# ESP32-S3_AT_UWB_Pro_with_Display_v1_0.net
KiCad netlist of a schematic drawn in EAGLE
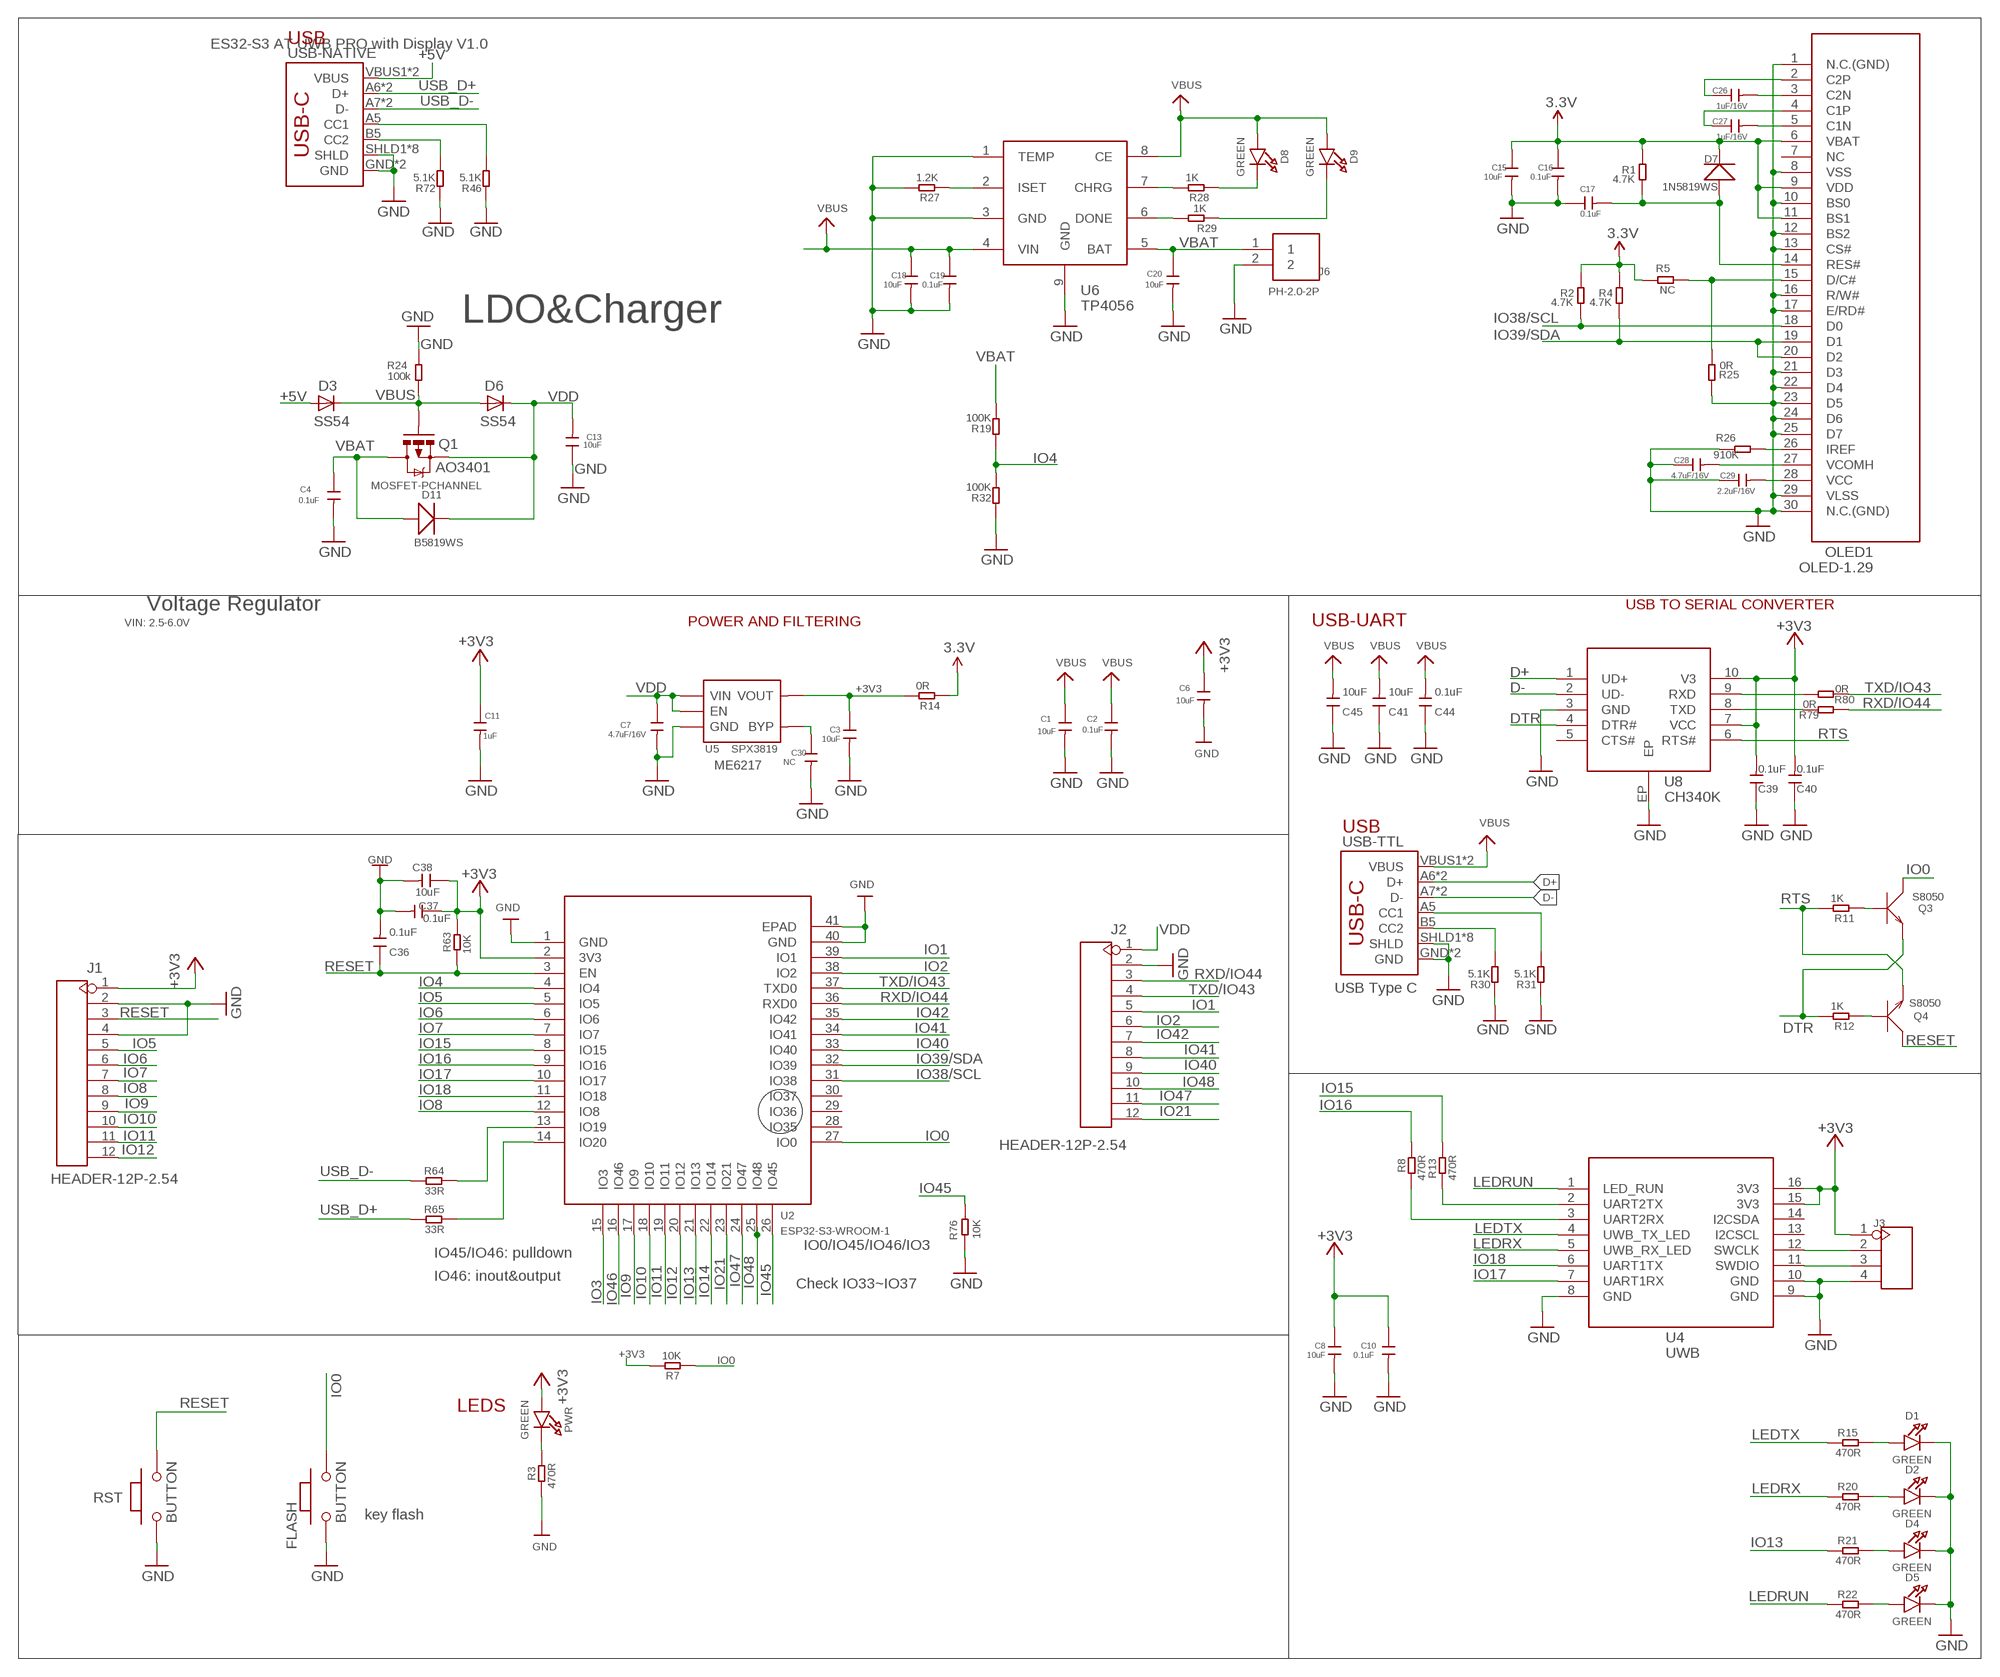
[diagram p0: schematic, sheet 1]

(export (version "E")
  (design (tool "Eeschema 10.0.6"))
  (components
    (comp (ref "C1")
      (value "10uF")
      (footprint "eagle-import:0603")
      (libsource (lib "eagle-import") (part "C-0603"))
    )
    (comp (ref "C2")
      (value "0.1uF")
      (footprint "eagle-import:0603")
      (libsource (lib "eagle-import") (part "C-0603"))
    )
    (comp (ref "C3")
      (value "10uF")
      (footprint "eagle-import:0603")
      (libsource (lib "eagle-import") (part "C-0603"))
    )
    (comp (ref "C4")
      (value "0.1uF")
      (footprint "eagle-import:0603")
      (libsource (lib "eagle-import") (part "C-0603"))
    )
    (comp (ref "C6")
      (value "10uF")
      (footprint "eagle-import:0603")
      (libsource (lib "eagle-import") (part "C-0603"))
    )
    (comp (ref "C7")
      (value "4.7uF/16V")
      (footprint "eagle-import:0603")
      (libsource (lib "eagle-import") (part "C-0603"))
    )
    (comp (ref "C8")
      (value "10uF")
      (footprint "eagle-import:0603")
      (libsource (lib "eagle-import") (part "C-0603"))
    )
    (comp (ref "C10")
      (value "0.1uF")
      (footprint "eagle-import:0603")
      (libsource (lib "eagle-import") (part "C-0603"))
    )
    (comp (ref "C11")
      (value "1uF")
      (footprint "eagle-import:0603")
      (libsource (lib "eagle-import") (part "C-0603"))
    )
    (comp (ref "C13")
      (value "10uF")
      (footprint "eagle-import:0603")
      (libsource (lib "eagle-import") (part "C-0603"))
    )
    (comp (ref "C15")
      (value "10uF")
      (footprint "eagle-import:0603")
      (libsource (lib "eagle-import") (part "C-0603"))
    )
    (comp (ref "C16")
      (value "0.1uF")
      (footprint "eagle-import:0603")
      (libsource (lib "eagle-import") (part "C-0603"))
    )
    (comp (ref "C17")
      (value "0.1uF")
      (footprint "eagle-import:0603")
      (libsource (lib "eagle-import") (part "C-0603"))
    )
    (comp (ref "C18")
      (value "10uF")
      (footprint "eagle-import:0603")
      (libsource (lib "eagle-import") (part "C-0603"))
    )
    (comp (ref "C19")
      (value "0.1uF")
      (footprint "eagle-import:0603")
      (libsource (lib "eagle-import") (part "C-0603"))
    )
    (comp (ref "C20")
      (value "10uF")
      (footprint "eagle-import:0603")
      (libsource (lib "eagle-import") (part "C-0603"))
    )
    (comp (ref "C26")
      (value "1uF/16V")
      (footprint "eagle-import:0603")
      (libsource (lib "eagle-import") (part "C-0603"))
    )
    (comp (ref "C27")
      (value "1uF/16V")
      (footprint "eagle-import:0603")
      (libsource (lib "eagle-import") (part "C-0603"))
    )
    (comp (ref "C28")
      (value "4.7uF/16V")
      (footprint "eagle-import:0603")
      (libsource (lib "eagle-import") (part "C-0603"))
    )
    (comp (ref "C29")
      (value "2.2uF/16V")
      (footprint "eagle-import:0603")
      (libsource (lib "eagle-import") (part "C-0603"))
    )
    (comp (ref "C30")
      (value "NC")
      (footprint "eagle-import:0603")
      (libsource (lib "eagle-import") (part "C-0603"))
    )
    (comp (ref "C36")
      (value "0.1uF")
      (footprint "eagle-import:DISCRETE_C0603")
      (libsource (lib "eagle-import") (part "DISCRETE_C-0603"))
    )
    (comp (ref "C37")
      (value "0.1uF")
      (footprint "eagle-import:DISCRETE_C0603")
      (libsource (lib "eagle-import") (part "DISCRETE_C-0603"))
    )
    (comp (ref "C38")
      (value "10uF")
      (footprint "eagle-import:DISCRETE_C0603")
      (libsource (lib "eagle-import") (part "DISCRETE_C-0603"))
    )
    (comp (ref "C39")
      (value "0.1uF")
      (footprint "eagle-import:DISCRETE_C0603")
      (libsource (lib "eagle-import") (part "DISCRETE_C-0603"))
    )
    (comp (ref "C40")
      (value "0.1uF")
      (footprint "eagle-import:DISCRETE_C0603")
      (libsource (lib "eagle-import") (part "DISCRETE_C-0603"))
    )
    (comp (ref "C41")
      (value "10uF")
      (footprint "eagle-import:DISCRETE_C0603")
      (libsource (lib "eagle-import") (part "DISCRETE_C-0603"))
    )
    (comp (ref "C44")
      (value "0.1uF")
      (footprint "eagle-import:DISCRETE_C0603")
      (libsource (lib "eagle-import") (part "DISCRETE_C-0603"))
    )
    (comp (ref "C45")
      (value "10uF")
      (footprint "eagle-import:DISCRETE_C0603")
      (libsource (lib "eagle-import") (part "DISCRETE_C-0603"))
    )
    (comp (ref "D1")
      (value "GREEN")
      (footprint "eagle-import:CHIPLED_0805_NOOUTLINE")
      (libsource (lib "eagle-import") (part "LED0805_NOOUTLINE"))
    )
    (comp (ref "D2")
      (value "GREEN")
      (footprint "eagle-import:CHIPLED_0805_NOOUTLINE")
      (libsource (lib "eagle-import") (part "LED0805_NOOUTLINE"))
    )
    (comp (ref "D3")
      (value "SS54")
      (footprint "eagle-import:DO-214AC")
      (libsource (lib "eagle-import") (part "DIODE-DO-214AC"))
    )
    (comp (ref "D4")
      (value "GREEN")
      (footprint "eagle-import:CHIPLED_0805_NOOUTLINE")
      (libsource (lib "eagle-import") (part "LED0805_NOOUTLINE"))
    )
    (comp (ref "D5")
      (value "GREEN")
      (footprint "eagle-import:CHIPLED_0805_NOOUTLINE")
      (libsource (lib "eagle-import") (part "LED0805_NOOUTLINE"))
    )
    (comp (ref "D6")
      (value "SS54")
      (footprint "eagle-import:DO-214AC")
      (libsource (lib "eagle-import") (part "DIODE-DO-214AC"))
    )
    (comp (ref "D7")
      (value "1N5819WS")
      (footprint "eagle-import:SOD323")
      (libsource (lib "eagle-import") (part "D'0805'"))
    )
    (comp (ref "D8")
      (value "GREEN")
      (footprint "eagle-import:CHIPLED_0805_NOOUTLINE")
      (libsource (lib "eagle-import") (part "LED0805_NOOUTLINE"))
    )
    (comp (ref "D9")
      (value "GREEN")
      (footprint "eagle-import:CHIPLED_0805_NOOUTLINE")
      (libsource (lib "eagle-import") (part "LED0805_NOOUTLINE"))
    )
    (comp (ref "D11")
      (value "B5819WS")
      (footprint "eagle-import:SOD323")
      (libsource (lib "eagle-import") (part "D'0805'"))
    )
    (comp (ref "FLASH")
      (value "BUTTON")
      (footprint "eagle-import:157SW")
      (libsource (lib "eagle-import") (part "PB157"))
    )
    (comp (ref "J1")
      (value "HEADER-12P-2.54")
      (footprint "eagle-import:12P-2.54")
      (libsource (lib "eagle-import") (part "HEADER-12P-2.54"))
    )
    (comp (ref "J2")
      (value "HEADER-12P-2.54")
      (footprint "eagle-import:12P-2.54")
      (libsource (lib "eagle-import") (part "HEADER-12P-2.54"))
    )
    (comp (ref "J3")
      (value "HEADER-4P-60/35MILROUND")
      (footprint "eagle-import:4P-65_35ROUND")
      (libsource (lib "eagle-import") (part "HEADER-4P-60/35MILROUND"))
    )
    (comp (ref "J6")
      (value "PH-2.0-2P")
      (footprint "eagle-import:PH-2.0-2P")
      (libsource (lib "eagle-import") (part "PH-2.0-2P"))
    )
    (comp (ref "OLED1")
      (value "OLED-1.29")
      (footprint "eagle-import:OLED-1.29")
      (libsource (lib "eagle-import") (part "OLED-1.29"))
    )
    (comp (ref "PWR")
      (value "GREEN")
      (footprint "eagle-import:CHIPLED_0805_NOOUTLINE")
      (libsource (lib "eagle-import") (part "LED0805_NOOUTLINE"))
    )
    (comp (ref "Q1")
      (value "MOSFET-PCHANNEL")
      (footprint "eagle-import:SOT23-3")
      (libsource (lib "eagle-import") (part "MOSFET-PCHANNEL"))
    )
    (comp (ref "Q3")
      (value "S8050")
      (footprint "eagle-import:SOT23")
      (libsource (lib "eagle-import") (part "TRANSISTOR-NPN-SOT23"))
    )
    (comp (ref "Q4")
      (value "S8050")
      (footprint "eagle-import:SOT23")
      (libsource (lib "eagle-import") (part "TRANSISTOR-NPN-SOT23"))
    )
    (comp (ref "R1")
      (value "4.7K")
      (footprint "eagle-import:R0603")
      (libsource (lib "eagle-import") (part "R-0603"))
    )
    (comp (ref "R2")
      (value "4.7K")
      (footprint "eagle-import:R0603")
      (libsource (lib "eagle-import") (part "R-0603"))
    )
    (comp (ref "R3")
      (value "470R")
      (footprint "eagle-import:R0603")
      (libsource (lib "eagle-import") (part "R-0603"))
    )
    (comp (ref "R4")
      (value "4.7K")
      (footprint "eagle-import:R0603")
      (libsource (lib "eagle-import") (part "R-0603"))
    )
    (comp (ref "R5")
      (value "NC")
      (footprint "eagle-import:R0603")
      (libsource (lib "eagle-import") (part "R-0603"))
    )
    (comp (ref "R7")
      (value "10K")
      (footprint "eagle-import:R0603")
      (libsource (lib "eagle-import") (part "R-0603"))
    )
    (comp (ref "R8")
      (value "470R")
      (footprint "eagle-import:R0603")
      (libsource (lib "eagle-import") (part "R-0603"))
    )
    (comp (ref "R11")
      (value "1K")
      (footprint "eagle-import:R0603")
      (libsource (lib "eagle-import") (part "R-0603"))
    )
    (comp (ref "R12")
      (value "1K")
      (footprint "eagle-import:R0603")
      (libsource (lib "eagle-import") (part "R-0603"))
    )
    (comp (ref "R13")
      (value "470R")
      (footprint "eagle-import:R0603")
      (libsource (lib "eagle-import") (part "R-0603"))
    )
    (comp (ref "R14")
      (value "0R")
      (footprint "eagle-import:R0603")
      (libsource (lib "eagle-import") (part "R-0603"))
    )
    (comp (ref "R15")
      (value "470R")
      (footprint "eagle-import:R0603")
      (libsource (lib "eagle-import") (part "R-0603"))
    )
    (comp (ref "R19")
      (value "100K")
      (footprint "eagle-import:DISCRETE_R0603")
      (libsource (lib "eagle-import") (part "DISCRETE_R-0603"))
    )
    (comp (ref "R20")
      (value "470R")
      (footprint "eagle-import:R0603")
      (libsource (lib "eagle-import") (part "R-0603"))
    )
    (comp (ref "R21")
      (value "470R")
      (footprint "eagle-import:R0603")
      (libsource (lib "eagle-import") (part "R-0603"))
    )
    (comp (ref "R22")
      (value "470R")
      (footprint "eagle-import:R0603")
      (libsource (lib "eagle-import") (part "R-0603"))
    )
    (comp (ref "R24")
      (value "100k")
      (footprint "eagle-import:R0603")
      (libsource (lib "eagle-import") (part "R-0603"))
    )
    (comp (ref "R25")
      (value "0R")
      (footprint "eagle-import:R0603")
      (libsource (lib "eagle-import") (part "R-0603"))
    )
    (comp (ref "R26")
      (value "910K")
      (footprint "eagle-import:R0603")
      (libsource (lib "eagle-import") (part "R-0603"))
    )
    (comp (ref "R27")
      (value "1.2K")
      (footprint "eagle-import:R0603")
      (libsource (lib "eagle-import") (part "R-0603"))
    )
    (comp (ref "R28")
      (value "1K")
      (footprint "eagle-import:R0603")
      (libsource (lib "eagle-import") (part "R-0603"))
    )
    (comp (ref "R29")
      (value "1K")
      (footprint "eagle-import:R0603")
      (libsource (lib "eagle-import") (part "R-0603"))
    )
    (comp (ref "R30")
      (value "5.1K")
      (footprint "eagle-import:DISCRETE_R0603")
      (libsource (lib "eagle-import") (part "DISCRETE_R-0603"))
    )
    (comp (ref "R31")
      (value "5.1K")
      (footprint "eagle-import:DISCRETE_R0603")
      (libsource (lib "eagle-import") (part "DISCRETE_R-0603"))
    )
    (comp (ref "R32")
      (value "100K")
      (footprint "eagle-import:DISCRETE_R0603")
      (libsource (lib "eagle-import") (part "DISCRETE_R-0603"))
    )
    (comp (ref "R46")
      (value "5.1K")
      (footprint "eagle-import:DISCRETE_R0603")
      (libsource (lib "eagle-import") (part "DISCRETE_R-0603"))
    )
    (comp (ref "R63")
      (value "10K")
      (footprint "eagle-import:R0603")
      (libsource (lib "eagle-import") (part "R-0603"))
    )
    (comp (ref "R64")
      (value "33R")
      (footprint "eagle-import:R0603")
      (libsource (lib "eagle-import") (part "R-0603"))
    )
    (comp (ref "R65")
      (value "33R")
      (footprint "eagle-import:R0603")
      (libsource (lib "eagle-import") (part "R-0603"))
    )
    (comp (ref "R72")
      (value "5.1K")
      (footprint "eagle-import:DISCRETE_R0603")
      (libsource (lib "eagle-import") (part "DISCRETE_R-0603"))
    )
    (comp (ref "R76")
      (value "10K")
      (footprint "eagle-import:R0603")
      (libsource (lib "eagle-import") (part "R-0603"))
    )
    (comp (ref "R79")
      (value "0R")
      (footprint "eagle-import:R0603")
      (libsource (lib "eagle-import") (part "R-0603"))
    )
    (comp (ref "R80")
      (value "0R")
      (footprint "eagle-import:R0603")
      (libsource (lib "eagle-import") (part "R-0603"))
    )
    (comp (ref "RST")
      (value "BUTTON")
      (footprint "eagle-import:157SW")
      (libsource (lib "eagle-import") (part "PB157"))
    )
    (comp (ref "U2")
      (value "ESP32-S3-WROOM-1")
      (footprint "eagle-import:ESP32-S3-WROOM-1")
      (libsource (lib "eagle-import") (part "ESP32-S3-WROOM-1"))
    )
    (comp (ref "U4")
      (value "UWB")
      (footprint "eagle-import:UWB")
      (libsource (lib "eagle-import") (part "UWB"))
    )
    (comp (ref "U5")
      (value "SPX3819")
      (footprint "eagle-import:SOT23-5")
      (libsource (lib "eagle-import") (part "SPX3819"))
    )
    (comp (ref "U6")
      (value "TP4056")
      (footprint "eagle-import:SOP8-1.27P")
      (libsource (lib "eagle-import") (part "TP4056"))
    )
    (comp (ref "U8")
      (value "CH340K")
      (footprint "eagle-import:ESOP-10-EP-150MIL")
      (libsource (lib "eagle-import") (part "CH340K"))
    )
    (comp (ref "USB-NATIVE")
      (value "USB_C5")
      (footprint "eagle-import:USB-C-16P-5")
      (libsource (lib "eagle-import") (part "USB_C5"))
    )
    (comp (ref "USB-TTL")
      (value "USB_C5")
      (footprint "eagle-import:USB-C-16P-5")
      (libsource (lib "eagle-import") (part "USB_C5"))
    )
  )
  (nets
    (net (code "1") (name "+3V3") (class "Default")
      (node (ref "C10") (pin "1") (pinfunction "1_1") (pintype "passive"))
      (node (ref "C11") (pin "1") (pinfunction "1_1") (pintype "passive"))
      (node (ref "C3") (pin "1") (pinfunction "1_1") (pintype "passive"))
      (node (ref "C37") (pin "1") (pinfunction "1_1") (pintype "passive"))
      (node (ref "C38") (pin "1") (pinfunction "1_1") (pintype "passive"))
      (node (ref "C39") (pin "2") (pinfunction "2_2") (pintype "passive"))
      (node (ref "C40") (pin "2") (pinfunction "2_2") (pintype "passive"))
      (node (ref "C6") (pin "1") (pinfunction "1_1") (pintype "passive"))
      (node (ref "C8") (pin "1") (pinfunction "1_1") (pintype "passive"))
      (node (ref "J1") (pin "1") (pinfunction "1_1") (pintype "bidirectional"))
      (node (ref "J3") (pin "1") (pinfunction "P$1_1") (pintype "bidirectional"))
      (node (ref "PWR") (pin "A") (pinfunction "A_A") (pintype "passive"))
      (node (ref "R14") (pin "2") (pinfunction "2_2") (pintype "passive"))
      (node (ref "R63") (pin "2") (pinfunction "2_2") (pintype "passive"))
      (node (ref "R7") (pin "2") (pinfunction "2_2") (pintype "passive"))
      (node (ref "U2") (pin "2") (pinfunction "3V3_2") (pintype "bidirectional"))
      (node (ref "U4") (pin "15") (pinfunction "3V3_15") (pintype "bidirectional"))
      (node (ref "U4") (pin "16") (pinfunction "3V3_16") (pintype "bidirectional"))
      (node (ref "U5") (pin "5") (pinfunction "VOUT_5") (pintype "bidirectional"))
      (node (ref "U8") (pin "10") (pinfunction "V3_10") (pintype "bidirectional"))
      (node (ref "U8") (pin "7") (pinfunction "VCC_7") (pintype "bidirectional"))
    )
    (net (code "2") (name "/+5V") (class "Default")
      (node (ref "D3") (pin "A") (pinfunction "A_A") (pintype "passive"))
      (node (ref "USB-NATIVE") (pin "VBUS1") (pinfunction "VBUS_VBUS1") (pintype "bidirectional"))
      (node (ref "USB-NATIVE") (pin "VBUS2") (pinfunction "VBUS_VBUS2") (pintype "bidirectional"))
    )
    (net (code "3") (name "/DTR") (class "Default")
      (node (ref "Q3") (pin "2") (pinfunction "E_2") (pintype "passive"))
      (node (ref "R12") (pin "2") (pinfunction "2_2") (pintype "passive"))
      (node (ref "U8") (pin "4") (pinfunction "DTR#_4") (pintype "bidirectional"))
    )
    (net (code "4") (name "/IO0") (class "Default")
      (node (ref "FLASH") (pin "2") (pinfunction "2_2") (pintype "passive"))
      (node (ref "Q3") (pin "3") (pinfunction "C_3") (pintype "passive"))
      (node (ref "R7") (pin "1") (pinfunction "1_1") (pintype "passive"))
      (node (ref "U2") (pin "27") (pinfunction "IO0_27") (pintype "bidirectional"))
    )
    (net (code "5") (name "/IO1") (class "Default")
      (node (ref "J2") (pin "5") (pinfunction "5_5") (pintype "bidirectional"))
      (node (ref "U2") (pin "39") (pinfunction "IO1_39") (pintype "bidirectional"))
    )
    (net (code "6") (name "/IO2") (class "Default")
      (node (ref "J2") (pin "6") (pinfunction "6_6") (pintype "bidirectional"))
      (node (ref "U2") (pin "38") (pinfunction "IO2_38") (pintype "bidirectional"))
    )
    (net (code "7") (name "/IO3") (class "Default")
      (node (ref "U2") (pin "15") (pinfunction "IO3_15") (pintype "bidirectional"))
    )
    (net (code "8") (name "/IO4") (class "Default")
      (node (ref "R19") (pin "1") (pinfunction "1_1") (pintype "passive"))
      (node (ref "R32") (pin "2") (pinfunction "2_2") (pintype "passive"))
      (node (ref "U2") (pin "4") (pinfunction "IO4_4") (pintype "bidirectional"))
    )
    (net (code "9") (name "/IO5") (class "Default")
      (node (ref "J1") (pin "5") (pinfunction "5_5") (pintype "bidirectional"))
      (node (ref "U2") (pin "5") (pinfunction "IO5_5") (pintype "bidirectional"))
    )
    (net (code "10") (name "/IO6") (class "Default")
      (node (ref "J1") (pin "6") (pinfunction "6_6") (pintype "bidirectional"))
      (node (ref "U2") (pin "6") (pinfunction "IO6_6") (pintype "bidirectional"))
    )
    (net (code "11") (name "/IO7") (class "Default")
      (node (ref "J1") (pin "7") (pinfunction "7_7") (pintype "bidirectional"))
      (node (ref "U2") (pin "7") (pinfunction "IO7_7") (pintype "bidirectional"))
    )
    (net (code "12") (name "/IO8") (class "Default")
      (node (ref "J1") (pin "8") (pinfunction "8_8") (pintype "bidirectional"))
      (node (ref "U2") (pin "12") (pinfunction "IO8_12") (pintype "bidirectional"))
    )
    (net (code "13") (name "/IO9") (class "Default")
      (node (ref "J1") (pin "9") (pinfunction "9_9") (pintype "bidirectional"))
      (node (ref "U2") (pin "17") (pinfunction "IO9_17") (pintype "bidirectional"))
    )
    (net (code "14") (name "/IO10") (class "Default")
      (node (ref "J1") (pin "10") (pinfunction "10_10") (pintype "bidirectional"))
      (node (ref "U2") (pin "18") (pinfunction "IO10_18") (pintype "bidirectional"))
    )
    (net (code "15") (name "/IO11") (class "Default")
      (node (ref "J1") (pin "11") (pinfunction "11_11") (pintype "bidirectional"))
      (node (ref "U2") (pin "19") (pinfunction "IO11_19") (pintype "bidirectional"))
    )
    (net (code "16") (name "/IO12") (class "Default")
      (node (ref "J1") (pin "12") (pinfunction "12_12") (pintype "bidirectional"))
      (node (ref "U2") (pin "20") (pinfunction "IO12_20") (pintype "bidirectional"))
    )
    (net (code "17") (name "/IO13") (class "Default")
      (node (ref "R21") (pin "1") (pinfunction "1_1") (pintype "passive"))
      (node (ref "U2") (pin "21") (pinfunction "IO13_21") (pintype "bidirectional"))
    )
    (net (code "18") (name "/IO14") (class "Default")
      (node (ref "U2") (pin "22") (pinfunction "IO14_22") (pintype "bidirectional"))
    )
    (net (code "19") (name "/IO15") (class "Default")
      (node (ref "R13") (pin "2") (pinfunction "2_2") (pintype "passive"))
      (node (ref "U2") (pin "8") (pinfunction "IO15_8") (pintype "bidirectional"))
    )
    (net (code "20") (name "/IO16") (class "Default")
      (node (ref "R8") (pin "2") (pinfunction "2_2") (pintype "passive"))
      (node (ref "U2") (pin "9") (pinfunction "IO16_9") (pintype "bidirectional"))
    )
    (net (code "21") (name "/IO17") (class "Default")
      (node (ref "U2") (pin "10") (pinfunction "IO17_10") (pintype "bidirectional"))
      (node (ref "U4") (pin "7") (pinfunction "UART1RX_7") (pintype "bidirectional"))
    )
    (net (code "22") (name "/IO18") (class "Default")
      (node (ref "U2") (pin "11") (pinfunction "IO18_11") (pintype "bidirectional"))
      (node (ref "U4") (pin "6") (pinfunction "UART1TX_6") (pintype "bidirectional"))
    )
    (net (code "23") (name "/IO21") (class "Default")
      (node (ref "J2") (pin "12") (pinfunction "12_12") (pintype "bidirectional"))
      (node (ref "U2") (pin "23") (pinfunction "IO21_23") (pintype "bidirectional"))
    )
    (net (code "24") (name "/IO38{slash}SCL") (class "Default")
      (node (ref "OLED1") (pin "18") (pinfunction "D0_18") (pintype "bidirectional"))
      (node (ref "R2") (pin "1") (pinfunction "1_1") (pintype "passive"))
      (node (ref "U2") (pin "31") (pinfunction "IO38_31") (pintype "bidirectional"))
    )
    (net (code "25") (name "/IO39{slash}SDA") (class "Default")
      (node (ref "OLED1") (pin "19") (pinfunction "D1_19") (pintype "bidirectional"))
      (node (ref "OLED1") (pin "20") (pinfunction "D2_20") (pintype "bidirectional"))
      (node (ref "R4") (pin "1") (pinfunction "1_1") (pintype "passive"))
      (node (ref "U2") (pin "32") (pinfunction "IO39_32") (pintype "bidirectional"))
    )
    (net (code "26") (name "/IO40") (class "Default")
      (node (ref "J2") (pin "9") (pinfunction "9_9") (pintype "bidirectional"))
      (node (ref "U2") (pin "33") (pinfunction "IO40_33") (pintype "bidirectional"))
    )
    (net (code "27") (name "/IO41") (class "Default")
      (node (ref "J2") (pin "8") (pinfunction "8_8") (pintype "bidirectional"))
      (node (ref "U2") (pin "34") (pinfunction "IO41_34") (pintype "bidirectional"))
    )
    (net (code "28") (name "/IO42") (class "Default")
      (node (ref "J2") (pin "7") (pinfunction "7_7") (pintype "bidirectional"))
      (node (ref "U2") (pin "35") (pinfunction "IO42_35") (pintype "bidirectional"))
    )
    (net (code "29") (name "/IO45") (class "Default")
      (node (ref "R76") (pin "2") (pinfunction "2_2") (pintype "passive"))
      (node (ref "U2") (pin "26") (pinfunction "IO45_26") (pintype "bidirectional"))
    )
    (net (code "30") (name "/IO46") (class "Default")
      (node (ref "U2") (pin "16") (pinfunction "IO46_16") (pintype "bidirectional"))
    )
    (net (code "31") (name "/IO47") (class "Default")
      (node (ref "J2") (pin "11") (pinfunction "11_11") (pintype "bidirectional"))
      (node (ref "U2") (pin "24") (pinfunction "IO47_24") (pintype "bidirectional"))
    )
    (net (code "32") (name "/IO48") (class "Default")
      (node (ref "J2") (pin "10") (pinfunction "10_10") (pintype "bidirectional"))
      (node (ref "U2") (pin "25") (pinfunction "IO48_25") (pintype "bidirectional"))
    )
    (net (code "33") (name "/LEDRUN") (class "Default")
      (node (ref "R22") (pin "1") (pinfunction "1_1") (pintype "passive"))
      (node (ref "U4") (pin "1") (pinfunction "LED_RUN_1") (pintype "bidirectional"))
    )
    (net (code "34") (name "/LEDRX") (class "Default")
      (node (ref "R20") (pin "1") (pinfunction "1_1") (pintype "passive"))
      (node (ref "U4") (pin "5") (pinfunction "UWB_RX_LED_5") (pintype "bidirectional"))
    )
    (net (code "35") (name "/LEDTX") (class "Default")
      (node (ref "R15") (pin "1") (pinfunction "1_1") (pintype "passive"))
      (node (ref "U4") (pin "4") (pinfunction "UWB_TX_LED_4") (pintype "bidirectional"))
    )
    (net (code "36") (name "/RESET") (class "Default")
      (node (ref "C36") (pin "1") (pinfunction "1_1") (pintype "passive"))
      (node (ref "J1") (pin "3") (pinfunction "3_3") (pintype "bidirectional"))
      (node (ref "Q4") (pin "3") (pinfunction "C_3") (pintype "passive"))
      (node (ref "R63") (pin "1") (pinfunction "1_1") (pintype "passive"))
      (node (ref "RST") (pin "2") (pinfunction "2_2") (pintype "passive"))
      (node (ref "U2") (pin "3") (pinfunction "EN_3") (pintype "bidirectional"))
    )
    (net (code "37") (name "/RTS") (class "Default")
      (node (ref "Q4") (pin "2") (pinfunction "E_2") (pintype "passive"))
      (node (ref "R11") (pin "2") (pinfunction "2_2") (pintype "passive"))
      (node (ref "U8") (pin "6") (pinfunction "RTS#_6") (pintype "bidirectional"))
    )
    (net (code "38") (name "/RXD{slash}IO44") (class "Default")
      (node (ref "J2") (pin "3") (pinfunction "3_3") (pintype "bidirectional"))
      (node (ref "R79") (pin "1") (pinfunction "1_1") (pintype "passive"))
      (node (ref "U2") (pin "36") (pinfunction "RXD0_36") (pintype "bidirectional"))
    )
    (net (code "39") (name "/TXD{slash}IO43") (class "Default")
      (node (ref "J2") (pin "4") (pinfunction "4_4") (pintype "bidirectional"))
      (node (ref "R80") (pin "1") (pinfunction "1_1") (pintype "passive"))
      (node (ref "U2") (pin "37") (pinfunction "TXD0_37") (pintype "bidirectional"))
    )
    (net (code "40") (name "/USB_D+") (class "Default")
      (node (ref "R65") (pin "1") (pinfunction "1_1") (pintype "passive"))
      (node (ref "USB-NATIVE") (pin "A6") (pinfunction "D+_A6") (pintype "bidirectional"))
      (node (ref "USB-NATIVE") (pin "B6") (pinfunction "D+_B6") (pintype "bidirectional"))
    )
    (net (code "41") (name "/USB_D-") (class "Default")
      (node (ref "R64") (pin "1") (pinfunction "1_1") (pintype "passive"))
      (node (ref "USB-NATIVE") (pin "A7") (pinfunction "D-_A7") (pintype "bidirectional"))
      (node (ref "USB-NATIVE") (pin "B7") (pinfunction "D-_B7") (pintype "bidirectional"))
    )
    (net (code "42") (name "/VBAT") (class "Default")
      (node (ref "C20") (pin "1") (pinfunction "1_1") (pintype "passive"))
      (node (ref "C4") (pin "1") (pinfunction "1_1") (pintype "passive"))
      (node (ref "D11") (pin "+") (pinfunction "+_+") (pintype "passive"))
      (node (ref "J6") (pin "1") (pinfunction "1_1") (pintype "bidirectional"))
      (node (ref "Q1") (pin "3") (pinfunction "D_3") (pintype "passive"))
      (node (ref "R19") (pin "2") (pinfunction "2_2") (pintype "passive"))
      (node (ref "U6") (pin "5") (pinfunction "BAT_5") (pintype "bidirectional"))
    )
    (net (code "43") (name "/VDD") (class "Default")
      (node (ref "C13") (pin "2") (pinfunction "2_2") (pintype "passive"))
      (node (ref "C7") (pin "1") (pinfunction "1_1") (pintype "passive"))
      (node (ref "D11") (pin "-") (pinfunction "-_-") (pintype "passive"))
      (node (ref "D6") (pin "C") (pinfunction "C_C") (pintype "passive"))
      (node (ref "J2") (pin "1") (pinfunction "1_1") (pintype "bidirectional"))
      (node (ref "Q1") (pin "2") (pinfunction "S_2") (pintype "passive"))
      (node (ref "U5") (pin "1") (pinfunction "VIN_1") (pintype "bidirectional"))
      (node (ref "U5") (pin "3") (pinfunction "EN_3") (pintype "bidirectional"))
    )
    (net (code "44") (name "3.3V") (class "Default")
      (node (ref "C15") (pin "1") (pinfunction "1_1") (pintype "passive"))
      (node (ref "C16") (pin "1") (pinfunction "1_1") (pintype "passive"))
      (node (ref "D7") (pin "-") (pinfunction "-_-") (pintype "passive"))
      (node (ref "OLED1") (pin "11") (pinfunction "BS1_11") (pintype "bidirectional"))
      (node (ref "OLED1") (pin "6") (pinfunction "VBAT_6") (pintype "bidirectional"))
      (node (ref "OLED1") (pin "9") (pinfunction "VDD_9") (pintype "bidirectional"))
      (node (ref "R1") (pin "2") (pinfunction "2_2") (pintype "passive"))
      (node (ref "R14") (pin "1") (pinfunction "1_1") (pintype "passive"))
      (node (ref "R2") (pin "2") (pinfunction "2_2") (pintype "passive"))
      (node (ref "R4") (pin "2") (pinfunction "2_2") (pintype "passive"))
      (node (ref "R5") (pin "2") (pinfunction "2_2") (pintype "passive"))
    )
    (net (code "45") (name "D+") (class "Default")
      (node (ref "U8") (pin "1") (pinfunction "UD+_1") (pintype "bidirectional"))
      (node (ref "USB-TTL") (pin "A6") (pinfunction "D+_A6") (pintype "bidirectional"))
      (node (ref "USB-TTL") (pin "B6") (pinfunction "D+_B6") (pintype "bidirectional"))
    )
    (net (code "46") (name "D-") (class "Default")
      (node (ref "U8") (pin "2") (pinfunction "UD-_2") (pintype "bidirectional"))
      (node (ref "USB-TTL") (pin "A7") (pinfunction "D-_A7") (pintype "bidirectional"))
      (node (ref "USB-TTL") (pin "B7") (pinfunction "D-_B7") (pintype "bidirectional"))
    )
    (net (code "47") (name "GND") (class "Default")
      (node (ref "C1") (pin "2") (pinfunction "2_2") (pintype "passive"))
      (node (ref "C10") (pin "2") (pinfunction "2_2") (pintype "passive"))
      (node (ref "C11") (pin "2") (pinfunction "2_2") (pintype "passive"))
      (node (ref "C13") (pin "1") (pinfunction "1_1") (pintype "passive"))
      (node (ref "C15") (pin "2") (pinfunction "2_2") (pintype "passive"))
      (node (ref "C16") (pin "2") (pinfunction "2_2") (pintype "passive"))
      (node (ref "C17") (pin "1") (pinfunction "1_1") (pintype "passive"))
      (node (ref "C18") (pin "2") (pinfunction "2_2") (pintype "passive"))
      (node (ref "C19") (pin "2") (pinfunction "2_2") (pintype "passive"))
      (node (ref "C2") (pin "2") (pinfunction "2_2") (pintype "passive"))
      (node (ref "C20") (pin "2") (pinfunction "2_2") (pintype "passive"))
      (node (ref "C28") (pin "1") (pinfunction "1_1") (pintype "passive"))
      (node (ref "C29") (pin "1") (pinfunction "1_1") (pintype "passive"))
      (node (ref "C3") (pin "2") (pinfunction "2_2") (pintype "passive"))
      (node (ref "C30") (pin "2") (pinfunction "2_2") (pintype "passive"))
      (node (ref "C36") (pin "2") (pinfunction "2_2") (pintype "passive"))
      (node (ref "C37") (pin "2") (pinfunction "2_2") (pintype "passive"))
      (node (ref "C38") (pin "2") (pinfunction "2_2") (pintype "passive"))
      (node (ref "C39") (pin "1") (pinfunction "1_1") (pintype "passive"))
      (node (ref "C4") (pin "2") (pinfunction "2_2") (pintype "passive"))
      (node (ref "C40") (pin "1") (pinfunction "1_1") (pintype "passive"))
      (node (ref "C41") (pin "1") (pinfunction "1_1") (pintype "passive"))
      (node (ref "C44") (pin "1") (pinfunction "1_1") (pintype "passive"))
      (node (ref "C45") (pin "1") (pinfunction "1_1") (pintype "passive"))
      (node (ref "C6") (pin "2") (pinfunction "2_2") (pintype "passive"))
      (node (ref "C7") (pin "2") (pinfunction "2_2") (pintype "passive"))
      (node (ref "C8") (pin "2") (pinfunction "2_2") (pintype "passive"))
      (node (ref "D1") (pin "C") (pinfunction "C_C") (pintype "passive"))
      (node (ref "D2") (pin "C") (pinfunction "C_C") (pintype "passive"))
      (node (ref "D4") (pin "C") (pinfunction "C_C") (pintype "passive"))
      (node (ref "D5") (pin "C") (pinfunction "C_C") (pintype "passive"))
      (node (ref "FLASH") (pin "1") (pinfunction "1_1") (pintype "passive"))
      (node (ref "J1") (pin "2") (pinfunction "2_2") (pintype "bidirectional"))
      (node (ref "J1") (pin "4") (pinfunction "4_4") (pintype "bidirectional"))
      (node (ref "J2") (pin "2") (pinfunction "2_2") (pintype "bidirectional"))
      (node (ref "J3") (pin "4") (pinfunction "P$4_4") (pintype "bidirectional"))
      (node (ref "J6") (pin "2") (pinfunction "2_2") (pintype "bidirectional"))
      (node (ref "OLED1") (pin "1") (pinfunction "N.C.(GND)_1") (pintype "bidirectional"))
      (node (ref "OLED1") (pin "10") (pinfunction "BS0_10") (pintype "bidirectional"))
      (node (ref "OLED1") (pin "12") (pinfunction "BS2_12") (pintype "bidirectional"))
      (node (ref "OLED1") (pin "13") (pinfunction "CS#_13") (pintype "bidirectional"))
      (node (ref "OLED1") (pin "16") (pinfunction "R/W#_16") (pintype "bidirectional"))
      (node (ref "OLED1") (pin "17") (pinfunction "E/RD#_17") (pintype "bidirectional"))
      (node (ref "OLED1") (pin "21") (pinfunction "D3_21") (pintype "bidirectional"))
      (node (ref "OLED1") (pin "22") (pinfunction "D4_22") (pintype "bidirectional"))
      (node (ref "OLED1") (pin "23") (pinfunction "D5_23") (pintype "bidirectional"))
      (node (ref "OLED1") (pin "24") (pinfunction "D6_24") (pintype "bidirectional"))
      (node (ref "OLED1") (pin "25") (pinfunction "D7_25") (pintype "bidirectional"))
      (node (ref "OLED1") (pin "29") (pinfunction "VLSS_29") (pintype "bidirectional"))
      (node (ref "OLED1") (pin "30") (pinfunction "N.C.(GND)_30") (pintype "bidirectional"))
      (node (ref "OLED1") (pin "8") (pinfunction "VSS_8") (pintype "bidirectional"))
      (node (ref "R24") (pin "2") (pinfunction "2_2") (pintype "passive"))
      (node (ref "R25") (pin "2") (pinfunction "2_2") (pintype "passive"))
      (node (ref "R26") (pin "2") (pinfunction "2_2") (pintype "passive"))
      (node (ref "R27") (pin "2") (pinfunction "2_2") (pintype "passive"))
      (node (ref "R3") (pin "1") (pinfunction "1_1") (pintype "passive"))
      (node (ref "R30") (pin "1") (pinfunction "1_1") (pintype "passive"))
      (node (ref "R31") (pin "1") (pinfunction "1_1") (pintype "passive"))
      (node (ref "R32") (pin "1") (pinfunction "1_1") (pintype "passive"))
      (node (ref "R46") (pin "1") (pinfunction "1_1") (pintype "passive"))
      (node (ref "R72") (pin "1") (pinfunction "1_1") (pintype "passive"))
      (node (ref "R76") (pin "1") (pinfunction "1_1") (pintype "passive"))
      (node (ref "RST") (pin "1") (pinfunction "1_1") (pintype "passive"))
      (node (ref "U2") (pin "1") (pinfunction "GND_1") (pintype "bidirectional"))
      (node (ref "U2") (pin "40") (pinfunction "GND_40") (pintype "bidirectional"))
      (node (ref "U2") (pin "41") (pinfunction "EPAD_41") (pintype "bidirectional"))
      (node (ref "U4") (pin "10") (pinfunction "GND_10") (pintype "bidirectional"))
      (node (ref "U4") (pin "8") (pinfunction "GND_8") (pintype "bidirectional"))
      (node (ref "U4") (pin "9") (pinfunction "GND_9") (pintype "bidirectional"))
      (node (ref "U5") (pin "2") (pinfunction "GND_2") (pintype "bidirectional"))
      (node (ref "U6") (pin "1") (pinfunction "TEMP_1") (pintype "bidirectional"))
      (node (ref "U6") (pin "3") (pinfunction "GND_3") (pintype "bidirectional"))
      (node (ref "U6") (pin "9") (pinfunction "GND_9") (pintype "bidirectional"))
      (node (ref "U8") (pin "3") (pinfunction "GND_3") (pintype "bidirectional"))
      (node (ref "U8") (pin "EP") (pinfunction "EP_EP") (pintype "bidirectional"))
      (node (ref "USB-NATIVE") (pin "GND") (pinfunction "GND_GND") (pintype "bidirectional"))
      (node (ref "USB-NATIVE") (pin "GND2") (pinfunction "GND_GND2") (pintype "bidirectional"))
      (node (ref "USB-NATIVE") (pin "SHLD1") (pinfunction "SHLD_SHLD1") (pintype "bidirectional"))
      (node (ref "USB-NATIVE") (pin "SHLD2") (pinfunction "SHLD_SHLD2") (pintype "bidirectional"))
      (node (ref "USB-NATIVE") (pin "SHLD3") (pinfunction "SHLD_SHLD3") (pintype "bidirectional"))
      (node (ref "USB-NATIVE") (pin "SHLD4") (pinfunction "SHLD_SHLD4") (pintype "bidirectional"))
      (node (ref "USB-NATIVE") (pin "SHLD5") (pinfunction "SHLD_SHLD5") (pintype "bidirectional"))
      (node (ref "USB-NATIVE") (pin "SHLD6") (pinfunction "SHLD_SHLD6") (pintype "bidirectional"))
      (node (ref "USB-NATIVE") (pin "SHLD7") (pinfunction "SHLD_SHLD7") (pintype "bidirectional"))
      (node (ref "USB-NATIVE") (pin "SHLD8") (pinfunction "SHLD_SHLD8") (pintype "bidirectional"))
      (node (ref "USB-TTL") (pin "GND") (pinfunction "GND_GND") (pintype "bidirectional"))
      (node (ref "USB-TTL") (pin "GND2") (pinfunction "GND_GND2") (pintype "bidirectional"))
      (node (ref "USB-TTL") (pin "SHLD1") (pinfunction "SHLD_SHLD1") (pintype "bidirectional"))
      (node (ref "USB-TTL") (pin "SHLD2") (pinfunction "SHLD_SHLD2") (pintype "bidirectional"))
      (node (ref "USB-TTL") (pin "SHLD3") (pinfunction "SHLD_SHLD3") (pintype "bidirectional"))
      (node (ref "USB-TTL") (pin "SHLD4") (pinfunction "SHLD_SHLD4") (pintype "bidirectional"))
      (node (ref "USB-TTL") (pin "SHLD5") (pinfunction "SHLD_SHLD5") (pintype "bidirectional"))
      (node (ref "USB-TTL") (pin "SHLD6") (pinfunction "SHLD_SHLD6") (pintype "bidirectional"))
      (node (ref "USB-TTL") (pin "SHLD7") (pinfunction "SHLD_SHLD7") (pintype "bidirectional"))
      (node (ref "USB-TTL") (pin "SHLD8") (pinfunction "SHLD_SHLD8") (pintype "bidirectional"))
    )
    (net (code "48") (name "Net-(D1-PadA)") (class "Default")
      (node (ref "D1") (pin "A") (pinfunction "A_A") (pintype "passive"))
      (node (ref "R15") (pin "2") (pinfunction "2_2") (pintype "passive"))
    )
    (net (code "49") (name "Net-(D2-PadA)") (class "Default")
      (node (ref "D2") (pin "A") (pinfunction "A_A") (pintype "passive"))
      (node (ref "R20") (pin "2") (pinfunction "2_2") (pintype "passive"))
    )
    (net (code "50") (name "Net-(D4-PadA)") (class "Default")
      (node (ref "D4") (pin "A") (pinfunction "A_A") (pintype "passive"))
      (node (ref "R21") (pin "2") (pinfunction "2_2") (pintype "passive"))
    )
    (net (code "51") (name "Net-(D5-PadA)") (class "Default")
      (node (ref "D5") (pin "A") (pinfunction "A_A") (pintype "passive"))
      (node (ref "R22") (pin "2") (pinfunction "2_2") (pintype "passive"))
    )
    (net (code "52") (name "Net-(D8-PadC)") (class "Default")
      (node (ref "D8") (pin "C") (pinfunction "C_C") (pintype "passive"))
      (node (ref "R28") (pin "1") (pinfunction "1_1") (pintype "passive"))
    )
    (net (code "53") (name "Net-(D9-PadC)") (class "Default")
      (node (ref "D9") (pin "C") (pinfunction "C_C") (pintype "passive"))
      (node (ref "R29") (pin "1") (pinfunction "1_1") (pintype "passive"))
    )
    (net (code "54") (name "Net-(J3-P$2)") (class "Default")
      (node (ref "J3") (pin "2") (pinfunction "P$2_2") (pintype "bidirectional"))
      (node (ref "U4") (pin "12") (pinfunction "SWCLK_12") (pintype "bidirectional"))
    )
    (net (code "55") (name "Net-(J3-P$3)") (class "Default")
      (node (ref "J3") (pin "3") (pinfunction "P$3_3") (pintype "bidirectional"))
      (node (ref "U4") (pin "11") (pinfunction "SWDIO_11") (pintype "bidirectional"))
    )
    (net (code "56") (name "Net-(OLED1-C1N)") (class "Default")
      (node (ref "C27") (pin "2") (pinfunction "2_2") (pintype "passive"))
      (node (ref "OLED1") (pin "5") (pinfunction "C1N_5") (pintype "bidirectional"))
    )
    (net (code "57") (name "Net-(OLED1-C1P)") (class "Default")
      (node (ref "C27") (pin "1") (pinfunction "1_1") (pintype "passive"))
      (node (ref "OLED1") (pin "4") (pinfunction "C1P_4") (pintype "bidirectional"))
    )
    (net (code "58") (name "Net-(OLED1-C2N)") (class "Default")
      (node (ref "C26") (pin "2") (pinfunction "2_2") (pintype "passive"))
      (node (ref "OLED1") (pin "3") (pinfunction "C2N_3") (pintype "bidirectional"))
    )
    (net (code "59") (name "Net-(OLED1-C2P)") (class "Default")
      (node (ref "C26") (pin "1") (pinfunction "1_1") (pintype "passive"))
      (node (ref "OLED1") (pin "2") (pinfunction "C2P_2") (pintype "bidirectional"))
    )
    (net (code "60") (name "Net-(OLED1-D{slash}C#)") (class "Default")
      (node (ref "OLED1") (pin "15") (pinfunction "D/C#_15") (pintype "bidirectional"))
      (node (ref "R25") (pin "1") (pinfunction "1_1") (pintype "passive"))
      (node (ref "R5") (pin "1") (pinfunction "1_1") (pintype "passive"))
    )
    (net (code "61") (name "Net-(OLED1-IREF)") (class "Default")
      (node (ref "OLED1") (pin "26") (pinfunction "IREF_26") (pintype "bidirectional"))
      (node (ref "R26") (pin "1") (pinfunction "1_1") (pintype "passive"))
    )
    (net (code "62") (name "Net-(OLED1-RES#)") (class "Default")
      (node (ref "C17") (pin "2") (pinfunction "2_2") (pintype "passive"))
      (node (ref "D7") (pin "+") (pinfunction "+_+") (pintype "passive"))
      (node (ref "OLED1") (pin "14") (pinfunction "RES#_14") (pintype "bidirectional"))
      (node (ref "R1") (pin "1") (pinfunction "1_1") (pintype "passive"))
    )
    (net (code "63") (name "Net-(OLED1-VCC)") (class "Default")
      (node (ref "C29") (pin "2") (pinfunction "2_2") (pintype "passive"))
      (node (ref "OLED1") (pin "28") (pinfunction "VCC_28") (pintype "bidirectional"))
    )
    (net (code "64") (name "Net-(OLED1-VCOMH)") (class "Default")
      (node (ref "C28") (pin "2") (pinfunction "2_2") (pintype "passive"))
      (node (ref "OLED1") (pin "27") (pinfunction "VCOMH_27") (pintype "bidirectional"))
    )
    (net (code "65") (name "Net-(PWR-PadC)") (class "Default")
      (node (ref "PWR") (pin "C") (pinfunction "C_C") (pintype "passive"))
      (node (ref "R3") (pin "2") (pinfunction "2_2") (pintype "passive"))
    )
    (net (code "66") (name "Net-(Q3-B)") (class "Default")
      (node (ref "Q3") (pin "1") (pinfunction "B_1") (pintype "passive"))
      (node (ref "R11") (pin "1") (pinfunction "1_1") (pintype "passive"))
    )
    (net (code "67") (name "Net-(Q4-B)") (class "Default")
      (node (ref "Q4") (pin "1") (pinfunction "B_1") (pintype "passive"))
      (node (ref "R12") (pin "1") (pinfunction "1_1") (pintype "passive"))
    )
    (net (code "68") (name "Net-(U2-IO19)") (class "Default")
      (node (ref "R64") (pin "2") (pinfunction "2_2") (pintype "passive"))
      (node (ref "U2") (pin "13") (pinfunction "IO19_13") (pintype "bidirectional"))
    )
    (net (code "69") (name "Net-(U2-IO20)") (class "Default")
      (node (ref "R65") (pin "2") (pinfunction "2_2") (pintype "passive"))
      (node (ref "U2") (pin "14") (pinfunction "IO20_14") (pintype "bidirectional"))
    )
    (net (code "70") (name "Net-(U4-UART2RX)") (class "Default")
      (node (ref "R8") (pin "1") (pinfunction "1_1") (pintype "passive"))
      (node (ref "U4") (pin "3") (pinfunction "UART2RX_3") (pintype "bidirectional"))
    )
    (net (code "71") (name "Net-(U4-UART2TX)") (class "Default")
      (node (ref "R13") (pin "1") (pinfunction "1_1") (pintype "passive"))
      (node (ref "U4") (pin "2") (pinfunction "UART2TX_2") (pintype "bidirectional"))
    )
    (net (code "72") (name "Net-(U5-BYP)") (class "Default")
      (node (ref "C30") (pin "1") (pinfunction "1_1") (pintype "passive"))
      (node (ref "U5") (pin "4") (pinfunction "BYP_4") (pintype "bidirectional"))
    )
    (net (code "73") (name "Net-(U6-CHRG)") (class "Default")
      (node (ref "R28") (pin "2") (pinfunction "2_2") (pintype "passive"))
      (node (ref "U6") (pin "7") (pinfunction "CHRG_7") (pintype "bidirectional"))
    )
    (net (code "74") (name "Net-(U6-DONE)") (class "Default")
      (node (ref "R29") (pin "2") (pinfunction "2_2") (pintype "passive"))
      (node (ref "U6") (pin "6") (pinfunction "DONE_6") (pintype "bidirectional"))
    )
    (net (code "75") (name "Net-(U6-ISET)") (class "Default")
      (node (ref "R27") (pin "1") (pinfunction "1_1") (pintype "passive"))
      (node (ref "U6") (pin "2") (pinfunction "ISET_2") (pintype "bidirectional"))
    )
    (net (code "76") (name "Net-(U8-RXD)") (class "Default")
      (node (ref "R80") (pin "2") (pinfunction "2_2") (pintype "passive"))
      (node (ref "U8") (pin "9") (pinfunction "RXD_9") (pintype "bidirectional"))
    )
    (net (code "77") (name "Net-(U8-TXD)") (class "Default")
      (node (ref "R79") (pin "2") (pinfunction "2_2") (pintype "passive"))
      (node (ref "U8") (pin "8") (pinfunction "TXD_8") (pintype "bidirectional"))
    )
    (net (code "78") (name "Net-(USB-NATIVE-CC1)") (class "Default")
      (node (ref "R46") (pin "2") (pinfunction "2_2") (pintype "passive"))
      (node (ref "USB-NATIVE") (pin "A5") (pinfunction "CC1_A5") (pintype "bidirectional"))
    )
    (net (code "79") (name "Net-(USB-NATIVE-CC2)") (class "Default")
      (node (ref "R72") (pin "2") (pinfunction "2_2") (pintype "passive"))
      (node (ref "USB-NATIVE") (pin "B5") (pinfunction "CC2_B5") (pintype "bidirectional"))
    )
    (net (code "80") (name "Net-(USB-TTL-CC1)") (class "Default")
      (node (ref "R31") (pin "2") (pinfunction "2_2") (pintype "passive"))
      (node (ref "USB-TTL") (pin "A5") (pinfunction "CC1_A5") (pintype "bidirectional"))
    )
    (net (code "81") (name "Net-(USB-TTL-CC2)") (class "Default")
      (node (ref "R30") (pin "2") (pinfunction "2_2") (pintype "passive"))
      (node (ref "USB-TTL") (pin "B5") (pinfunction "CC2_B5") (pintype "bidirectional"))
    )
    (net (code "82") (name "VBUS") (class "Default")
      (node (ref "C1") (pin "1") (pinfunction "1_1") (pintype "passive"))
      (node (ref "C18") (pin "1") (pinfunction "1_1") (pintype "passive"))
      (node (ref "C19") (pin "1") (pinfunction "1_1") (pintype "passive"))
      (node (ref "C2") (pin "1") (pinfunction "1_1") (pintype "passive"))
      (node (ref "C41") (pin "2") (pinfunction "2_2") (pintype "passive"))
      (node (ref "C44") (pin "2") (pinfunction "2_2") (pintype "passive"))
      (node (ref "C45") (pin "2") (pinfunction "2_2") (pintype "passive"))
      (node (ref "D3") (pin "C") (pinfunction "C_C") (pintype "passive"))
      (node (ref "D6") (pin "A") (pinfunction "A_A") (pintype "passive"))
      (node (ref "D8") (pin "A") (pinfunction "A_A") (pintype "passive"))
      (node (ref "D9") (pin "A") (pinfunction "A_A") (pintype "passive"))
      (node (ref "Q1") (pin "1") (pinfunction "G_1") (pintype "passive"))
      (node (ref "R24") (pin "1") (pinfunction "1_1") (pintype "passive"))
      (node (ref "U6") (pin "4") (pinfunction "VIN_4") (pintype "bidirectional"))
      (node (ref "U6") (pin "8") (pinfunction "CE_8") (pintype "bidirectional"))
      (node (ref "USB-TTL") (pin "VBUS1") (pinfunction "VBUS_VBUS1") (pintype "bidirectional"))
      (node (ref "USB-TTL") (pin "VBUS2") (pinfunction "VBUS_VBUS2") (pintype "bidirectional"))
    )
    (net (code "83") (name "unconnected-(OLED1-NC-Pad7)") (class "Default")
      (node (ref "OLED1") (pin "7") (pinfunction "NC_7") (pintype "bidirectional"))
    )
    (net (code "84") (name "unconnected-(U2-IO35-Pad28)") (class "Default")
      (node (ref "U2") (pin "28") (pinfunction "IO35_28") (pintype "bidirectional"))
    )
    (net (code "85") (name "unconnected-(U2-IO36-Pad29)") (class "Default")
      (node (ref "U2") (pin "29") (pinfunction "IO36_29") (pintype "bidirectional"))
    )
    (net (code "86") (name "unconnected-(U2-IO37-Pad30)") (class "Default")
      (node (ref "U2") (pin "30") (pinfunction "IO37_30") (pintype "bidirectional"))
    )
    (net (code "87") (name "unconnected-(U4-I2CSCL-Pad13)") (class "Default")
      (node (ref "U4") (pin "13") (pinfunction "I2CSCL_13") (pintype "bidirectional"))
    )
    (net (code "88") (name "unconnected-(U4-I2CSDA-Pad14)") (class "Default")
      (node (ref "U4") (pin "14") (pinfunction "I2CSDA_14") (pintype "bidirectional"))
    )
    (net (code "89") (name "unconnected-(U8-CTS#-Pad5)") (class "Default")
      (node (ref "U8") (pin "5") (pinfunction "CTS#_5") (pintype "bidirectional"))
    )
  )
)
